# design.net
KiCad netlist of a schematic drawn in Altium Designer
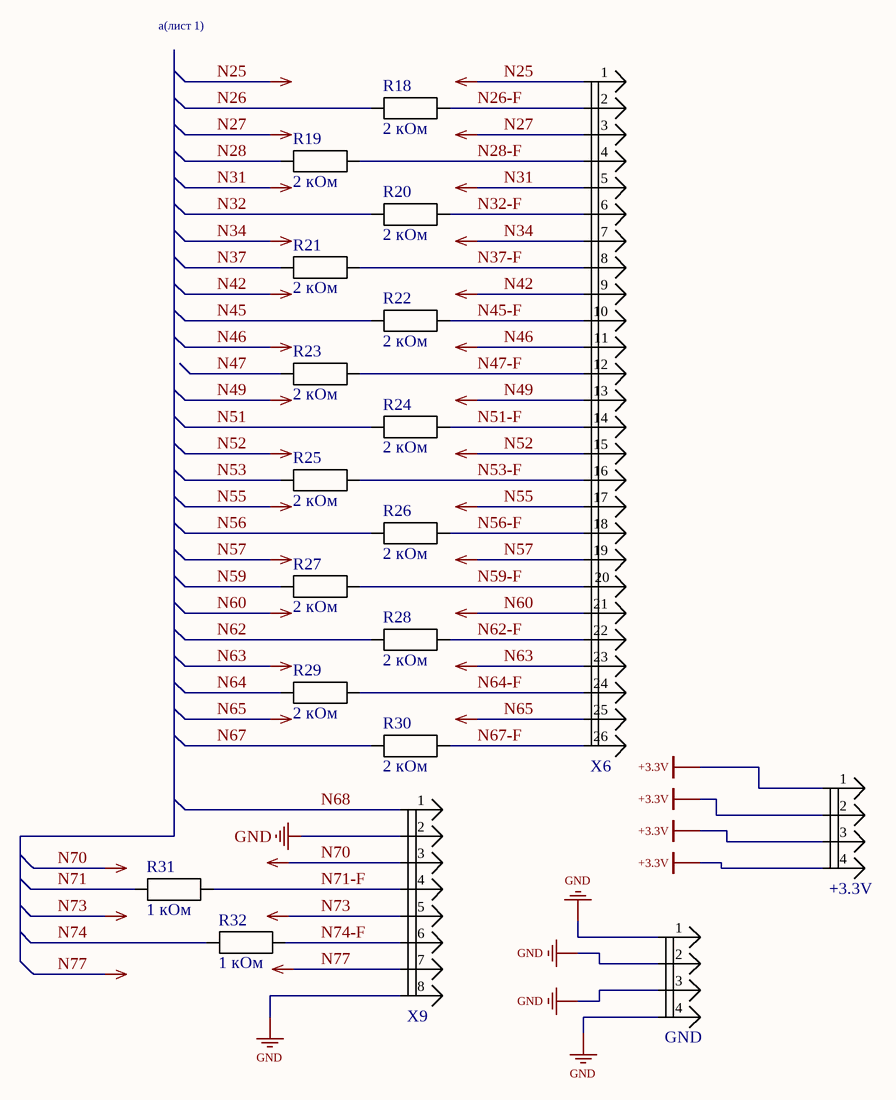
[diagram p0: Внешние разъемы.SchDoc]

(export (version "E")
  (design (tool "Eeschema 10.0.6"))
  (components
    (comp (ref "+3.3V")
      (value "~")
      (footprint "СНП346-4ВП21-1")
      (fields
        (field (name "PARTNUMBER") "РЮМК.430420.011ТУ")
        (field (name "MANUFACTURERPARTNUMBER") "Вилка СНП346-4ВП21-1")
      )
      (libsource (lib "РАЗЪЕМЫ") (part "СНП346-4ВП21-1"))
    )
    (comp (ref "GND")
      (value "~")
      (footprint "СНП346-4ВП21-1")
      (fields
        (field (name "PARTNUMBER") "РЮМК.430420.011ТУ")
        (field (name "MANUFACTURERPARTNUMBER") "Вилка СНП346-4ВП21-1")
      )
      (libsource (lib "РАЗЪЕМЫ") (part "СНП346-4ВП21-1"))
    )
    (comp (ref "R18")
      (value "2 кОм")
      (footprint "Р1-12-0,125")
      (fields
        (field (name "TOLERANCE") "±1%-Л")
        (field (name "PARTNUMBER") "АЛЯР.434110.005 ТУ")
        (field (name "MANUFACTURERPARTNUMBER") "Р1-12-0,125-1,5 кОм±1%-Л")
      )
      (libsource (lib "РЕЗИСТОРЫ") (part "Р1-12-0,125-1,5 кОм±1%"))
    )
    (comp (ref "R19")
      (value "2 кОм")
      (footprint "Р1-12-0,125")
      (fields
        (field (name "TOLERANCE") "±1%-Л")
        (field (name "PARTNUMBER") "АЛЯР.434110.005 ТУ")
        (field (name "MANUFACTURERPARTNUMBER") "Р1-12-0,125-1,5 кОм±1%-Л")
      )
      (libsource (lib "РЕЗИСТОРЫ") (part "Р1-12-0,125-1,5 кОм±1%"))
    )
    (comp (ref "R20")
      (value "2 кОм")
      (footprint "Р1-12-0,125")
      (fields
        (field (name "TOLERANCE") "±1%-Л")
        (field (name "PARTNUMBER") "АЛЯР.434110.005 ТУ")
        (field (name "MANUFACTURERPARTNUMBER") "Р1-12-0,125-1,5 кОм±1%-Л")
      )
      (libsource (lib "РЕЗИСТОРЫ") (part "Р1-12-0,125-1,5 кОм±1%"))
    )
    (comp (ref "R21")
      (value "2 кОм")
      (footprint "Р1-12-0,125")
      (fields
        (field (name "TOLERANCE") "±1%-Л")
        (field (name "PARTNUMBER") "АЛЯР.434110.005 ТУ")
        (field (name "MANUFACTURERPARTNUMBER") "Р1-12-0,125-1,5 кОм±1%-Л")
      )
      (libsource (lib "РЕЗИСТОРЫ") (part "Р1-12-0,125-1,5 кОм±1%"))
    )
    (comp (ref "R22")
      (value "2 кОм")
      (footprint "Р1-12-0,125")
      (fields
        (field (name "TOLERANCE") "±1%-Л")
        (field (name "PARTNUMBER") "АЛЯР.434110.005 ТУ")
        (field (name "MANUFACTURERPARTNUMBER") "Р1-12-0,125-1,5 кОм±1%-Л")
      )
      (libsource (lib "РЕЗИСТОРЫ") (part "Р1-12-0,125-1,5 кОм±1%"))
    )
    (comp (ref "R23")
      (value "2 кОм")
      (footprint "Р1-12-0,125")
      (fields
        (field (name "TOLERANCE") "±1%-Л")
        (field (name "PARTNUMBER") "АЛЯР.434110.005 ТУ")
        (field (name "MANUFACTURERPARTNUMBER") "Р1-12-0,125-1,5 кОм±1%-Л")
      )
      (libsource (lib "РЕЗИСТОРЫ") (part "Р1-12-0,125-1,5 кОм±1%"))
    )
    (comp (ref "R24")
      (value "2 кОм")
      (footprint "Р1-12-0,125")
      (fields
        (field (name "TOLERANCE") "±1%-Л")
        (field (name "PARTNUMBER") "АЛЯР.434110.005 ТУ")
        (field (name "MANUFACTURERPARTNUMBER") "Р1-12-0,125-1,5 кОм±1%-Л")
      )
      (libsource (lib "РЕЗИСТОРЫ") (part "Р1-12-0,125-1,5 кОм±1%"))
    )
    (comp (ref "R25")
      (value "2 кОм")
      (footprint "Р1-12-0,125")
      (fields
        (field (name "TOLERANCE") "±1%-Л")
        (field (name "PARTNUMBER") "АЛЯР.434110.005 ТУ")
        (field (name "MANUFACTURERPARTNUMBER") "Р1-12-0,125-1,5 кОм±1%-Л")
      )
      (libsource (lib "РЕЗИСТОРЫ") (part "Р1-12-0,125-1,5 кОм±1%"))
    )
    (comp (ref "R26")
      (value "2 кОм")
      (footprint "Р1-12-0,125")
      (fields
        (field (name "TOLERANCE") "±1%-Л")
        (field (name "PARTNUMBER") "АЛЯР.434110.005 ТУ")
        (field (name "MANUFACTURERPARTNUMBER") "Р1-12-0,125-1,5 кОм±1%-Л")
      )
      (libsource (lib "РЕЗИСТОРЫ") (part "Р1-12-0,125-1,5 кОм±1%"))
    )
    (comp (ref "R27")
      (value "2 кОм")
      (footprint "Р1-12-0,125")
      (fields
        (field (name "TOLERANCE") "±1%-Л")
        (field (name "PARTNUMBER") "АЛЯР.434110.005 ТУ")
        (field (name "MANUFACTURERPARTNUMBER") "Р1-12-0,125-1,5 кОм±1%-Л")
      )
      (libsource (lib "РЕЗИСТОРЫ") (part "Р1-12-0,125-1,5 кОм±1%"))
    )
    (comp (ref "R28")
      (value "2 кОм")
      (footprint "Р1-12-0,125")
      (fields
        (field (name "TOLERANCE") "±1%-Л")
        (field (name "PARTNUMBER") "АЛЯР.434110.005 ТУ")
        (field (name "MANUFACTURERPARTNUMBER") "Р1-12-0,125-1,5 кОм±1%-Л")
      )
      (libsource (lib "РЕЗИСТОРЫ") (part "Р1-12-0,125-1,5 кОм±1%"))
    )
    (comp (ref "R29")
      (value "2 кОм")
      (footprint "Р1-12-0,125")
      (fields
        (field (name "TOLERANCE") "±1%-Л")
        (field (name "PARTNUMBER") "АЛЯР.434110.005 ТУ")
        (field (name "MANUFACTURERPARTNUMBER") "Р1-12-0,125-1,5 кОм±1%-Л")
      )
      (libsource (lib "РЕЗИСТОРЫ") (part "Р1-12-0,125-1,5 кОм±1%"))
    )
    (comp (ref "R30")
      (value "2 кОм")
      (footprint "Р1-12-0,125")
      (fields
        (field (name "TOLERANCE") "±1%-Л")
        (field (name "PARTNUMBER") "АЛЯР.434110.005 ТУ")
        (field (name "MANUFACTURERPARTNUMBER") "Р1-12-0,125-1,5 кОм±1%-Л")
      )
      (libsource (lib "РЕЗИСТОРЫ") (part "Р1-12-0,125-1,5 кОм±1%"))
    )
    (comp (ref "R31")
      (value "1 кОм")
      (footprint "Р1-12-0,125")
      (fields
        (field (name "TOLERANCE") "±1%-Л")
        (field (name "PARTNUMBER") "АЛЯР.434110.005 ТУ")
        (field (name "MANUFACTURERPARTNUMBER") "Р1-12-0,125-1,5 кОм±1%-Л")
      )
      (libsource (lib "РЕЗИСТОРЫ") (part "Р1-12-0,125-1,5 кОм±1%"))
    )
    (comp (ref "R32")
      (value "1 кОм")
      (footprint "Р1-12-0,125")
      (fields
        (field (name "TOLERANCE") "±1%-Л")
        (field (name "PARTNUMBER") "АЛЯР.434110.005 ТУ")
        (field (name "MANUFACTURERPARTNUMBER") "Р1-12-0,125-1,5 кОм±1%-Л")
      )
      (libsource (lib "РЕЗИСТОРЫ") (part "Р1-12-0,125-1,5 кОм±1%"))
    )
    (comp (ref "X6")
      (value "~")
      (footprint "СНП346-26ВП21-2")
      (fields
        (field (name "PARTNUMBER") "РЮМК.430420.011ТУ")
        (field (name "MANUFACTURERPARTNUMBER") "Вилка СНП346-10ВП21-2")
      )
      (libsource (lib "РАЗЪЕМЫ") (part "СНП346-26ВП21-2_1_1"))
    )
    (comp (ref "X9")
      (value "~")
      (footprint "СНП346-8ВП21-2")
      (fields
        (field (name "PARTNUMBER") "РЮМК.430420.011ТУ")
        (field (name "MANUFACTURERPARTNUMBER") "Вилка СНП346-8ВП21-2")
      )
      (libsource (lib "РАЗЪЕМЫ") (part "СНП346-8ВП21-2"))
    )
  )
  (nets
    (net (code "1") (name "+3.3V") (class "Default")
      (node (ref "+3.3V") (pin "1") (pinfunction "1_1") (pintype "passive"))
      (node (ref "+3.3V") (pin "2") (pinfunction "2_2") (pintype "passive"))
      (node (ref "+3.3V") (pin "3") (pinfunction "3_3") (pintype "passive"))
      (node (ref "+3.3V") (pin "4") (pinfunction "4_4") (pintype "passive"))
    )
    (net (code "2") (name "/N26") (class "Default")
      (node (ref "R18") (pin "1") (pinfunction "1_1") (pintype "passive"))
    )
    (net (code "3") (name "/N26-F") (class "Default")
      (node (ref "R18") (pin "2") (pinfunction "2_2") (pintype "passive"))
      (node (ref "X6") (pin "2") (pinfunction "2_2") (pintype "passive"))
    )
    (net (code "4") (name "/N28") (class "Default")
      (node (ref "R19") (pin "1") (pinfunction "1_1") (pintype "passive"))
    )
    (net (code "5") (name "/N28-F") (class "Default")
      (node (ref "R19") (pin "2") (pinfunction "2_2") (pintype "passive"))
      (node (ref "X6") (pin "4") (pinfunction "4_4") (pintype "passive"))
    )
    (net (code "6") (name "/N32") (class "Default")
      (node (ref "R20") (pin "1") (pinfunction "1_1") (pintype "passive"))
    )
    (net (code "7") (name "/N32-F") (class "Default")
      (node (ref "R20") (pin "2") (pinfunction "2_2") (pintype "passive"))
      (node (ref "X6") (pin "6") (pinfunction "6_6") (pintype "passive"))
    )
    (net (code "8") (name "/N37") (class "Default")
      (node (ref "R21") (pin "1") (pinfunction "1_1") (pintype "passive"))
    )
    (net (code "9") (name "/N37-F") (class "Default")
      (node (ref "R21") (pin "2") (pinfunction "2_2") (pintype "passive"))
      (node (ref "X6") (pin "8") (pinfunction "8_8") (pintype "passive"))
    )
    (net (code "10") (name "/N45") (class "Default")
      (node (ref "R22") (pin "1") (pinfunction "1_1") (pintype "passive"))
    )
    (net (code "11") (name "/N45-F") (class "Default")
      (node (ref "R22") (pin "2") (pinfunction "2_2") (pintype "passive"))
      (node (ref "X6") (pin "10") (pinfunction "10_10") (pintype "passive"))
    )
    (net (code "12") (name "/N47") (class "Default")
      (node (ref "R23") (pin "1") (pinfunction "1_1") (pintype "passive"))
    )
    (net (code "13") (name "/N47-F") (class "Default")
      (node (ref "R23") (pin "2") (pinfunction "2_2") (pintype "passive"))
      (node (ref "X6") (pin "12") (pinfunction "12_12") (pintype "passive"))
    )
    (net (code "14") (name "/N51") (class "Default")
      (node (ref "R24") (pin "1") (pinfunction "1_1") (pintype "passive"))
    )
    (net (code "15") (name "/N51-F") (class "Default")
      (node (ref "R24") (pin "2") (pinfunction "2_2") (pintype "passive"))
      (node (ref "X6") (pin "14") (pinfunction "14_14") (pintype "passive"))
    )
    (net (code "16") (name "/N53") (class "Default")
      (node (ref "R25") (pin "1") (pinfunction "1_1") (pintype "passive"))
    )
    (net (code "17") (name "/N53-F") (class "Default")
      (node (ref "R25") (pin "2") (pinfunction "2_2") (pintype "passive"))
      (node (ref "X6") (pin "16") (pinfunction "16_16") (pintype "passive"))
    )
    (net (code "18") (name "/N56") (class "Default")
      (node (ref "R26") (pin "1") (pinfunction "1_1") (pintype "passive"))
    )
    (net (code "19") (name "/N56-F") (class "Default")
      (node (ref "R26") (pin "2") (pinfunction "2_2") (pintype "passive"))
      (node (ref "X6") (pin "18") (pinfunction "18_18") (pintype "passive"))
    )
    (net (code "20") (name "/N59") (class "Default")
      (node (ref "R27") (pin "1") (pinfunction "1_1") (pintype "passive"))
    )
    (net (code "21") (name "/N59-F") (class "Default")
      (node (ref "R27") (pin "2") (pinfunction "2_2") (pintype "passive"))
      (node (ref "X6") (pin "20") (pinfunction "20_20") (pintype "passive"))
    )
    (net (code "22") (name "/N62") (class "Default")
      (node (ref "R28") (pin "1") (pinfunction "1_1") (pintype "passive"))
    )
    (net (code "23") (name "/N62-F") (class "Default")
      (node (ref "R28") (pin "2") (pinfunction "2_2") (pintype "passive"))
      (node (ref "X6") (pin "22") (pinfunction "22_22") (pintype "passive"))
    )
    (net (code "24") (name "/N64") (class "Default")
      (node (ref "R29") (pin "1") (pinfunction "1_1") (pintype "passive"))
    )
    (net (code "25") (name "/N64-F") (class "Default")
      (node (ref "R29") (pin "2") (pinfunction "2_2") (pintype "passive"))
      (node (ref "X6") (pin "24") (pinfunction "24_24") (pintype "passive"))
    )
    (net (code "26") (name "/N67") (class "Default")
      (node (ref "R30") (pin "1") (pinfunction "1_1") (pintype "passive"))
    )
    (net (code "27") (name "/N67-F") (class "Default")
      (node (ref "R30") (pin "2") (pinfunction "2_2") (pintype "passive"))
      (node (ref "X6") (pin "26") (pinfunction "26_26") (pintype "passive"))
    )
    (net (code "28") (name "/N68") (class "Default")
      (node (ref "X9") (pin "1") (pinfunction "1_1") (pintype "passive"))
    )
    (net (code "29") (name "/N71") (class "Default")
      (node (ref "R31") (pin "1") (pinfunction "1_1") (pintype "passive"))
    )
    (net (code "30") (name "/N71-F") (class "Default")
      (node (ref "R31") (pin "2") (pinfunction "2_2") (pintype "passive"))
      (node (ref "X9") (pin "4") (pinfunction "4_4") (pintype "passive"))
    )
    (net (code "31") (name "/N74") (class "Default")
      (node (ref "R32") (pin "1") (pinfunction "1_1") (pintype "passive"))
    )
    (net (code "32") (name "/N74-F") (class "Default")
      (node (ref "R32") (pin "2") (pinfunction "2_2") (pintype "passive"))
      (node (ref "X9") (pin "6") (pinfunction "6_6") (pintype "passive"))
    )
    (net (code "33") (name "<NO NET>") (class "Default")
      (node (ref "X6") (pin "1") (pinfunction "1_1") (pintype "passive"))
      (node (ref "X6") (pin "11") (pinfunction "11_11") (pintype "passive"))
      (node (ref "X6") (pin "13") (pinfunction "13_13") (pintype "passive"))
      (node (ref "X6") (pin "15") (pinfunction "15_15") (pintype "passive"))
      (node (ref "X6") (pin "17") (pinfunction "17_17") (pintype "passive"))
      (node (ref "X6") (pin "19") (pinfunction "19_19") (pintype "passive"))
      (node (ref "X6") (pin "21") (pinfunction "21_21") (pintype "passive"))
      (node (ref "X6") (pin "23") (pinfunction "23_23") (pintype "passive"))
      (node (ref "X6") (pin "25") (pinfunction "25_25") (pintype "passive"))
      (node (ref "X6") (pin "3") (pinfunction "3_3") (pintype "passive"))
      (node (ref "X6") (pin "5") (pinfunction "5_5") (pintype "passive"))
      (node (ref "X6") (pin "7") (pinfunction "7_7") (pintype "passive"))
      (node (ref "X6") (pin "9") (pinfunction "9_9") (pintype "passive"))
      (node (ref "X9") (pin "3") (pinfunction "3_3") (pintype "passive"))
      (node (ref "X9") (pin "5") (pinfunction "5_5") (pintype "passive"))
      (node (ref "X9") (pin "7") (pinfunction "7_7") (pintype "passive"))
    )
    (net (code "34") (name "GND") (class "Default")
      (node (ref "GND") (pin "1") (pinfunction "1_1") (pintype "passive"))
      (node (ref "GND") (pin "2") (pinfunction "2_2") (pintype "passive"))
      (node (ref "GND") (pin "3") (pinfunction "3_3") (pintype "passive"))
      (node (ref "GND") (pin "4") (pinfunction "4_4") (pintype "passive"))
      (node (ref "X9") (pin "2") (pinfunction "2_2") (pintype "passive"))
      (node (ref "X9") (pin "8") (pinfunction "8_8") (pintype "passive"))
    )
  )
)
